# ADIS16209_v3.net
KiCad netlist of a schematic drawn in EAGLE
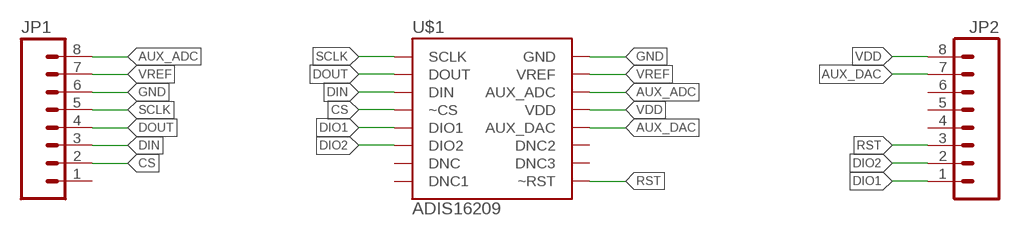
[diagram p0: schematic, sheet 1]

(export (version "E")
  (design (tool "Eeschema 10.0.6"))
  (components
    (comp (ref "JP1")
      (value "M08")
      (footprint "eagle-import:1X08")
      (libsource (lib "eagle-import") (part "M08"))
    )
    (comp (ref "JP2")
      (value "M08")
      (footprint "eagle-import:1X08")
      (libsource (lib "eagle-import") (part "M08"))
    )
    (comp (ref "U$1")
      (value "ADIS16209")
      (footprint "eagle-import:CC-16-2")
      (libsource (lib "eagle-import") (part "ADIS16209"))
    )
  )
  (nets
    (net (code "1") (name "AUX_ADC") (class "Default")
      (node (ref "JP1") (pin "8") (pinfunction "8_8") (pintype "passive"))
      (node (ref "U$1") (pin "P$14") (pinfunction "AUX_ADC_P$14") (pintype "bidirectional"))
    )
    (net (code "2") (name "AUX_DAC") (class "Default")
      (node (ref "JP2") (pin "7") (pinfunction "7_7") (pintype "passive"))
      (node (ref "U$1") (pin "P$12") (pinfunction "AUX_DAC_P$12") (pintype "bidirectional"))
    )
    (net (code "3") (name "CS") (class "Default")
      (node (ref "JP1") (pin "2") (pinfunction "2_2") (pintype "passive"))
      (node (ref "U$1") (pin "P$4") (pinfunction "~{CS}_P$4") (pintype "bidirectional"))
    )
    (net (code "4") (name "DIN") (class "Default")
      (node (ref "JP1") (pin "3") (pinfunction "3_3") (pintype "passive"))
      (node (ref "U$1") (pin "P$3") (pinfunction "DIN_P$3") (pintype "bidirectional"))
    )
    (net (code "5") (name "DIO1") (class "Default")
      (node (ref "JP2") (pin "1") (pinfunction "1_1") (pintype "passive"))
      (node (ref "U$1") (pin "P$5") (pinfunction "DIO1_P$5") (pintype "bidirectional"))
    )
    (net (code "6") (name "DIO2") (class "Default")
      (node (ref "JP2") (pin "2") (pinfunction "2_2") (pintype "passive"))
      (node (ref "U$1") (pin "P$6") (pinfunction "DIO2_P$6") (pintype "bidirectional"))
    )
    (net (code "7") (name "DOUT") (class "Default")
      (node (ref "JP1") (pin "4") (pinfunction "4_4") (pintype "passive"))
      (node (ref "U$1") (pin "P$2") (pinfunction "DOUT_P$2") (pintype "bidirectional"))
    )
    (net (code "8") (name "GND") (class "Default")
      (node (ref "JP1") (pin "6") (pinfunction "6_6") (pintype "passive"))
      (node (ref "U$1") (pin "P$16") (pinfunction "GND_P$16") (pintype "bidirectional"))
    )
    (net (code "9") (name "RST") (class "Default")
      (node (ref "JP2") (pin "3") (pinfunction "3_3") (pintype "passive"))
      (node (ref "U$1") (pin "P$9") (pinfunction "~{RST}_P$9") (pintype "bidirectional"))
    )
    (net (code "10") (name "SCLK") (class "Default")
      (node (ref "JP1") (pin "5") (pinfunction "5_5") (pintype "passive"))
      (node (ref "U$1") (pin "P$1") (pinfunction "SCLK_P$1") (pintype "bidirectional"))
    )
    (net (code "11") (name "VDD") (class "Default")
      (node (ref "JP2") (pin "8") (pinfunction "8_8") (pintype "passive"))
      (node (ref "U$1") (pin "P$13") (pinfunction "VDD_P$13") (pintype "bidirectional"))
    )
    (net (code "12") (name "VREF") (class "Default")
      (node (ref "JP1") (pin "7") (pinfunction "7_7") (pintype "passive"))
      (node (ref "U$1") (pin "P$15") (pinfunction "VREF_P$15") (pintype "bidirectional"))
    )
    (net (code "13") (name "unconnected-(JP1-Pad1)") (class "Default")
      (node (ref "JP1") (pin "1") (pinfunction "1_1") (pintype "passive"))
    )
    (net (code "14") (name "unconnected-(JP2-Pad4)") (class "Default")
      (node (ref "JP2") (pin "4") (pinfunction "4_4") (pintype "passive"))
    )
    (net (code "15") (name "unconnected-(JP2-Pad5)") (class "Default")
      (node (ref "JP2") (pin "5") (pinfunction "5_5") (pintype "passive"))
    )
    (net (code "16") (name "unconnected-(JP2-Pad6)") (class "Default")
      (node (ref "JP2") (pin "6") (pinfunction "6_6") (pintype "passive"))
    )
    (net (code "17") (name "unconnected-(U$1-DNC-PadP$7)") (class "Default")
      (node (ref "U$1") (pin "P$7") (pinfunction "DNC_P$7") (pintype "bidirectional"))
    )
    (net (code "18") (name "unconnected-(U$1-DNC1-PadP$8)") (class "Default")
      (node (ref "U$1") (pin "P$8") (pinfunction "DNC1_P$8") (pintype "bidirectional"))
    )
    (net (code "19") (name "unconnected-(U$1-DNC2-PadP$11)") (class "Default")
      (node (ref "U$1") (pin "P$11") (pinfunction "DNC2_P$11") (pintype "bidirectional"))
    )
    (net (code "20") (name "unconnected-(U$1-DNC3-PadP$10)") (class "Default")
      (node (ref "U$1") (pin "P$10") (pinfunction "DNC3_P$10") (pintype "bidirectional"))
    )
  )
)
